# leaf_chaser.net
KiCad netlist of a schematic drawn in EasyEDA Pro
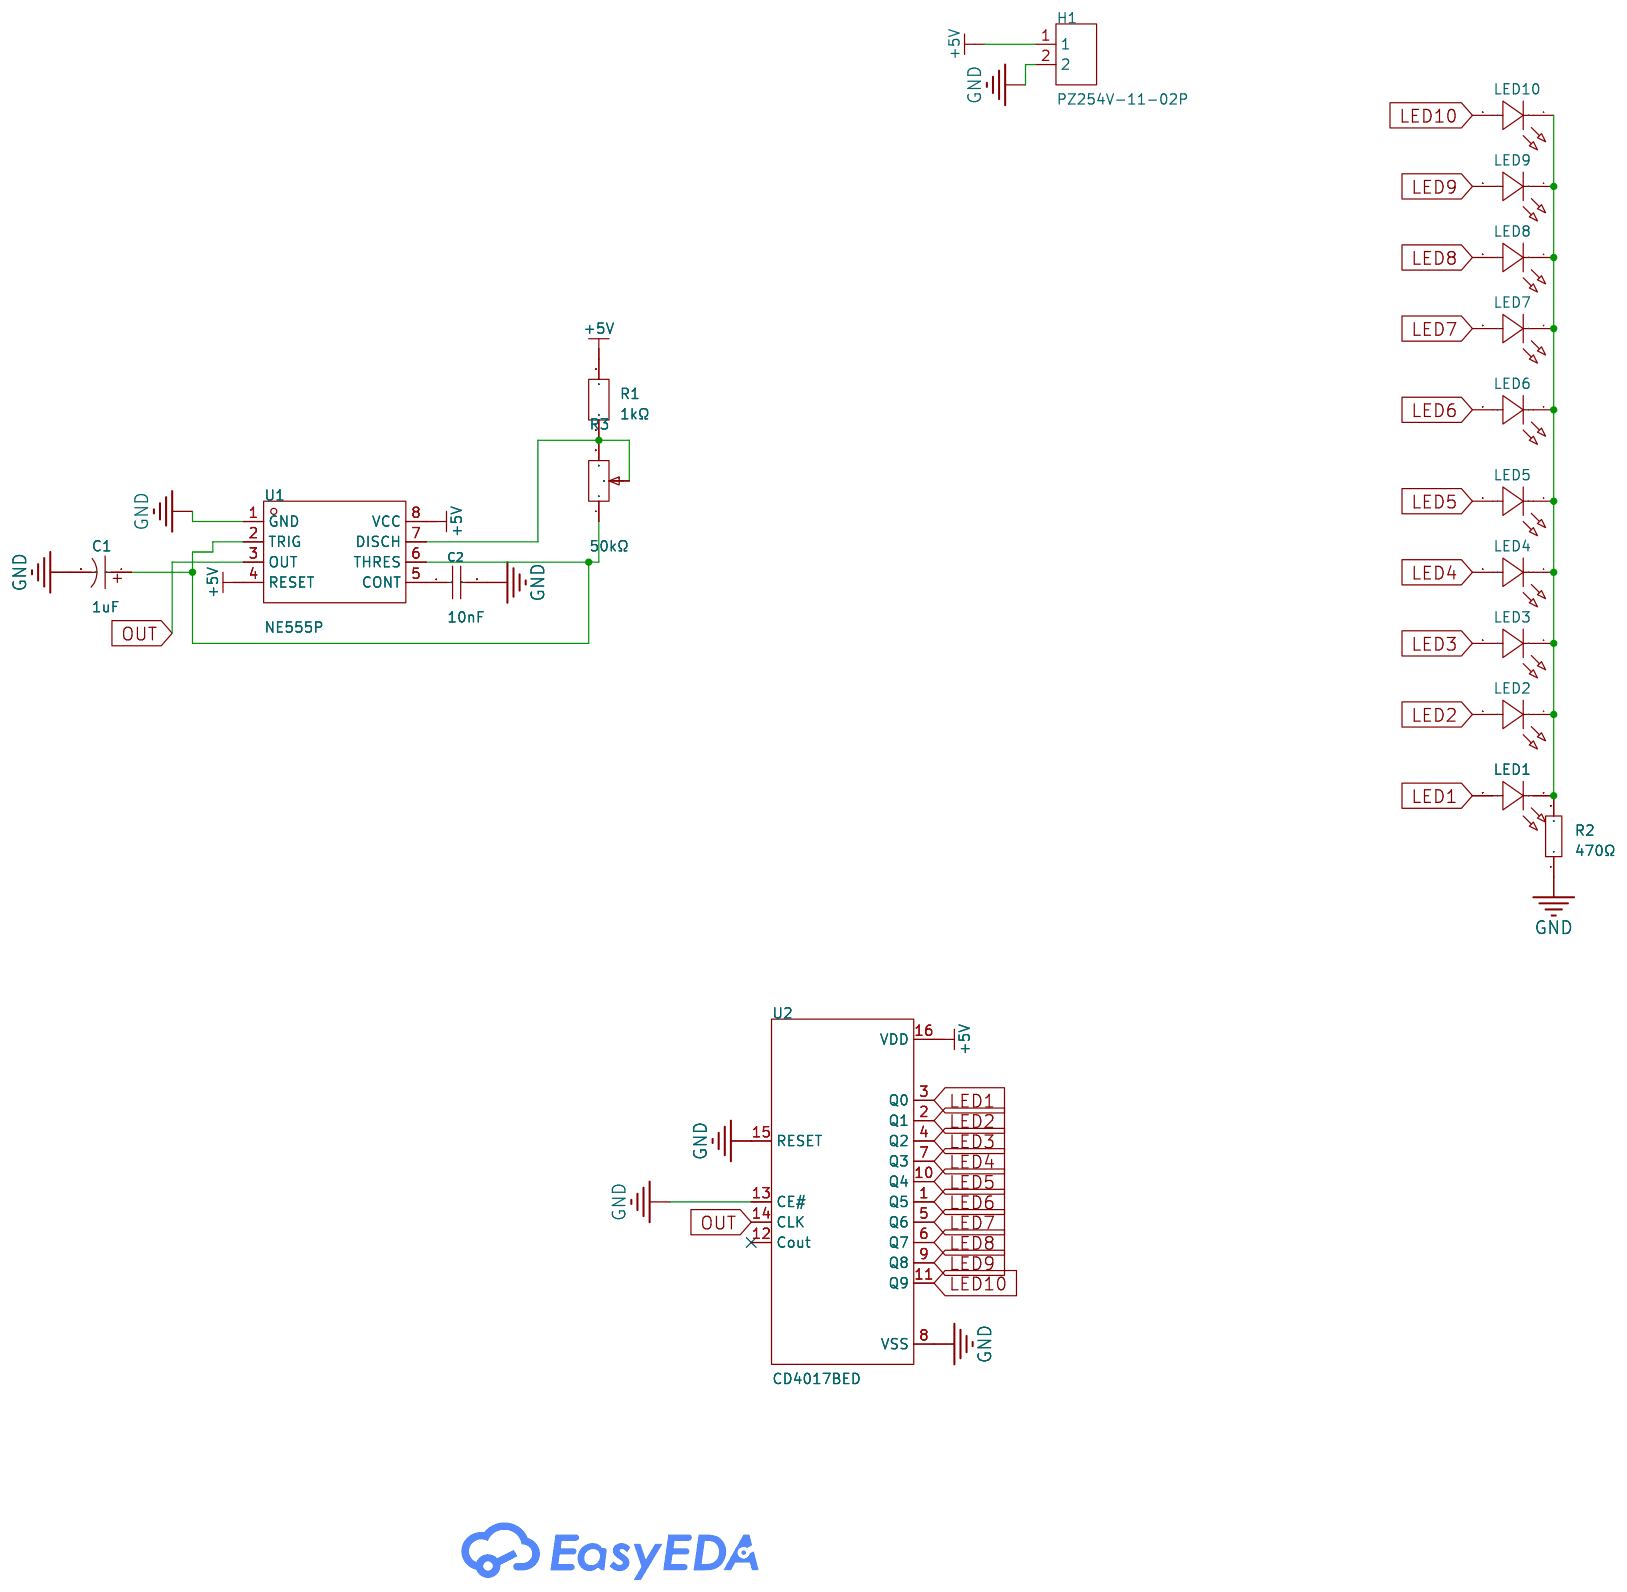
[diagram p0: schematic sheet]

(export (version "E")
  (design (tool "Eeschema 10.0.6"))
  (components
    (comp (ref "C1")
      (value "1uF")
      (footprint "easyedapro:CAP-TH_BD4.0-P1.50-D0.8-FD")
      (fields
        (field (name "Manufacturer Part") "KS1H010MB070A00CV0")
        (field (name "Manufacturer") "HUAWEI(华威集团)")
      )
      (libsource (lib "easyedapro") (part "KS1H010MB070A00CV0"))
    )
    (comp (ref "C2")
      (value "10nF")
      (footprint "easyedapro:C0603")
      (description "Capacitance:10nF Tolerance:±10% Tolerance:±10% Voltage Rating:50V Temperature Coefficient:X7R")
      (fields
        (field (name "Manufacturer Part") "CC0603KRX7R9BB103")
        (field (name "Manufacturer") "YAGEO(国巨)")
      )
      (libsource (lib "easyedapro") (part "CC0603KRX7R9BB103"))
    )
    (comp (ref "H1")
      (value "PZ254V-11-02P")
      (footprint "easyedapro:HDR-TH_2P-P2.54-V-M")
      (fields (field (name "Manufacturer") "XFCN(兴飞)"))
      (libsource (lib "easyedapro") (part "PZ254V-11-02P"))
    )
    (comp (ref "LED1")
      (value "XL-302SURD")
      (footprint "easyedapro:LED-TH_BD3.8-P2.54-RD")
      (fields (field (name "Manufacturer") "XINGLIGHT(成兴光)"))
      (libsource (lib "easyedapro") (part "XL-302SURD"))
    )
    (comp (ref "LED2")
      (value "XL-302SURD")
      (footprint "easyedapro:LED-TH_BD3.8-P2.54-RD")
      (fields (field (name "Manufacturer") "XINGLIGHT(成兴光)"))
      (libsource (lib "easyedapro") (part "XL-302SURD"))
    )
    (comp (ref "LED3")
      (value "XL-302SURD")
      (footprint "easyedapro:LED-TH_BD3.8-P2.54-RD")
      (fields (field (name "Manufacturer") "XINGLIGHT(成兴光)"))
      (libsource (lib "easyedapro") (part "XL-302SURD"))
    )
    (comp (ref "LED4")
      (value "XL-302SURD")
      (footprint "easyedapro:LED-TH_BD3.8-P2.54-RD")
      (fields (field (name "Manufacturer") "XINGLIGHT(成兴光)"))
      (libsource (lib "easyedapro") (part "XL-302SURD"))
    )
    (comp (ref "LED5")
      (value "XL-302SURD")
      (footprint "easyedapro:LED-TH_BD3.8-P2.54-RD")
      (fields (field (name "Manufacturer") "XINGLIGHT(成兴光)"))
      (libsource (lib "easyedapro") (part "XL-302SURD"))
    )
    (comp (ref "LED6")
      (value "XL-302SURD")
      (footprint "easyedapro:LED-TH_BD3.8-P2.54-RD")
      (fields (field (name "Manufacturer") "XINGLIGHT(成兴光)"))
      (libsource (lib "easyedapro") (part "XL-302SURD"))
    )
    (comp (ref "LED7")
      (value "XL-302SURD")
      (footprint "easyedapro:LED-TH_BD3.8-P2.54-RD")
      (fields (field (name "Manufacturer") "XINGLIGHT(成兴光)"))
      (libsource (lib "easyedapro") (part "XL-302SURD"))
    )
    (comp (ref "LED8")
      (value "XL-302SURD")
      (footprint "easyedapro:LED-TH_BD3.8-P2.54-RD")
      (fields (field (name "Manufacturer") "XINGLIGHT(成兴光)"))
      (libsource (lib "easyedapro") (part "XL-302SURD"))
    )
    (comp (ref "LED9")
      (value "XL-302SURD")
      (footprint "easyedapro:LED-TH_BD3.8-P2.54-RD")
      (fields (field (name "Manufacturer") "XINGLIGHT(成兴光)"))
      (libsource (lib "easyedapro") (part "XL-302SURD"))
    )
    (comp (ref "LED10")
      (value "XL-302SURD")
      (footprint "easyedapro:LED-TH_BD3.8-P2.54-RD")
      (fields (field (name "Manufacturer") "XINGLIGHT(成兴光)"))
      (libsource (lib "easyedapro") (part "XL-302SURD"))
    )
    (comp (ref "R1")
      (value "1kΩ")
      (footprint "easyedapro:RES-TH_BD2.7-L6.2-P10.20-D0.4")
      (fields (field (name "Manufacturer Part") "MF1/4W-1K±1%-ST52") (field (name "Manufacturer") "VO(翔胜)"))
      (libsource (lib "easyedapro") (part "MF1/4W-1K±1%-ST52"))
    )
    (comp (ref "R2")
      (value "470Ω")
      (footprint "easyedapro:RES-TH_BD2.3-L6.5-P10.50-D0.5")
      (fields
        (field (name "Manufacturer Part") "MF1/2WS-470Ω±1% T")
        (field (name "Manufacturer") "CCO(千志电子)")
      )
      (libsource (lib "easyedapro") (part "MF1/2WS-470Ω±1% T52"))
    )
    (comp (ref "R3")
      (value "50kΩ")
      (footprint "easyedapro:RES-ADJ-TH_3296W")
      (fields (field (name "Manufacturer Part") "3296W-1-503LF") (field (name "Manufacturer") "JIERR(捷而瑞)"))
      (libsource (lib "easyedapro") (part "3296W-1-503LF_C49190466"))
    )
    (comp (ref "U1")
      (value "NE555P")
      (footprint "easyedapro:DIP-8_L9.8-W6.6-P2.54-LS7.6-BL")
      (fields (field (name "Manufacturer") "TI(德州仪器)"))
      (libsource (lib "easyedapro") (part "NE555P"))
    )
    (comp (ref "U2")
      (value "CD4017BED")
      (footprint "easyedapro:PDIP-16_L19.7-W6.6-P2.54-LS7.6-BL")
      (fields (field (name "Manufacturer") "GMIC(绿微)"))
      (libsource (lib "easyedapro") (part "CD4017BED"))
    )
  )
  (nets
    (net (code "1") (name "+5V") (class "Default")
      (node (ref "H1") (pin "1") (pinfunction "1_1") (pintype "unspecified"))
      (node (ref "R1") (pin "2") (pinfunction "2_2") (pintype "unspecified"))
      (node (ref "U1") (pin "4") (pinfunction "RESET_4") (pintype "input"))
      (node (ref "U1") (pin "8") (pinfunction "VCC_8") (pintype "input"))
      (node (ref "U2") (pin "16") (pinfunction "VDD_16") (pintype "unspecified"))
    )
    (net (code "2") (name "GND") (class "Default")
      (node (ref "C1") (pin "2") (pinfunction "2_2") (pintype "input"))
      (node (ref "C2") (pin "2") (pinfunction "2_2") (pintype "input"))
      (node (ref "H1") (pin "2") (pinfunction "2_2") (pintype "unspecified"))
      (node (ref "R2") (pin "1") (pinfunction "1_1") (pintype "unspecified"))
      (node (ref "U1") (pin "1") (pinfunction "GND_1") (pintype "input"))
      (node (ref "U2") (pin "13") (pinfunction "CE#_13") (pintype "unspecified"))
      (node (ref "U2") (pin "15") (pinfunction "RESET_15") (pintype "unspecified"))
      (node (ref "U2") (pin "8") (pinfunction "VSS_8") (pintype "unspecified"))
    )
    (net (code "3") (name "LED1") (class "Default")
      (node (ref "LED1") (pin "2") (pinfunction "A_2") (pintype "unspecified"))
      (node (ref "U2") (pin "3") (pinfunction "Q0_3") (pintype "unspecified"))
    )
    (net (code "4") (name "LED2") (class "Default")
      (node (ref "LED2") (pin "2") (pinfunction "A_2") (pintype "unspecified"))
      (node (ref "U2") (pin "2") (pinfunction "Q1_2") (pintype "unspecified"))
    )
    (net (code "5") (name "LED3") (class "Default")
      (node (ref "LED3") (pin "2") (pinfunction "A_2") (pintype "unspecified"))
      (node (ref "U2") (pin "4") (pinfunction "Q2_4") (pintype "unspecified"))
    )
    (net (code "6") (name "LED4") (class "Default")
      (node (ref "LED4") (pin "2") (pinfunction "A_2") (pintype "unspecified"))
      (node (ref "U2") (pin "7") (pinfunction "Q3_7") (pintype "unspecified"))
    )
    (net (code "7") (name "LED5") (class "Default")
      (node (ref "LED5") (pin "2") (pinfunction "A_2") (pintype "unspecified"))
      (node (ref "U2") (pin "10") (pinfunction "Q4_10") (pintype "unspecified"))
    )
    (net (code "8") (name "LED6") (class "Default")
      (node (ref "LED6") (pin "2") (pinfunction "A_2") (pintype "unspecified"))
      (node (ref "U2") (pin "1") (pinfunction "Q5_1") (pintype "unspecified"))
    )
    (net (code "9") (name "LED7") (class "Default")
      (node (ref "LED7") (pin "2") (pinfunction "A_2") (pintype "unspecified"))
      (node (ref "U2") (pin "5") (pinfunction "Q6_5") (pintype "unspecified"))
    )
    (net (code "10") (name "LED8") (class "Default")
      (node (ref "LED8") (pin "2") (pinfunction "A_2") (pintype "unspecified"))
      (node (ref "U2") (pin "6") (pinfunction "Q7_6") (pintype "unspecified"))
    )
    (net (code "11") (name "LED9") (class "Default")
      (node (ref "LED9") (pin "2") (pinfunction "A_2") (pintype "unspecified"))
      (node (ref "U2") (pin "9") (pinfunction "Q8_9") (pintype "unspecified"))
    )
    (net (code "12") (name "LED10") (class "Default")
      (node (ref "LED10") (pin "2") (pinfunction "A_2") (pintype "unspecified"))
      (node (ref "U2") (pin "11") (pinfunction "Q9_11") (pintype "unspecified"))
    )
    (net (code "13") (name "Net-(LED1-K)") (class "Default")
      (node (ref "LED1") (pin "1") (pinfunction "K_1") (pintype "unspecified"))
      (node (ref "LED10") (pin "1") (pinfunction "K_1") (pintype "unspecified"))
      (node (ref "LED2") (pin "1") (pinfunction "K_1") (pintype "unspecified"))
      (node (ref "LED3") (pin "1") (pinfunction "K_1") (pintype "unspecified"))
      (node (ref "LED4") (pin "1") (pinfunction "K_1") (pintype "unspecified"))
      (node (ref "LED5") (pin "1") (pinfunction "K_1") (pintype "unspecified"))
      (node (ref "LED6") (pin "1") (pinfunction "K_1") (pintype "unspecified"))
      (node (ref "LED7") (pin "1") (pinfunction "K_1") (pintype "unspecified"))
      (node (ref "LED8") (pin "1") (pinfunction "K_1") (pintype "unspecified"))
      (node (ref "LED9") (pin "1") (pinfunction "K_1") (pintype "unspecified"))
      (node (ref "R2") (pin "2") (pinfunction "2_2") (pintype "unspecified"))
    )
    (net (code "14") (name "Net-(U1-CONT)") (class "Default")
      (node (ref "C2") (pin "1") (pinfunction "1_1") (pintype "input"))
      (node (ref "U1") (pin "5") (pinfunction "CONT_5") (pintype "input"))
    )
    (net (code "15") (name "Net-(U1-DISCH)") (class "Default")
      (node (ref "R1") (pin "1") (pinfunction "1_1") (pintype "unspecified"))
      (node (ref "R3") (pin "2") (pinfunction "2_2") (pintype "input"))
      (node (ref "R3") (pin "3") (pinfunction "3_3") (pintype "input"))
      (node (ref "U1") (pin "7") (pinfunction "DISCH_7") (pintype "input"))
    )
    (net (code "16") (name "Net-(U1-THRES)") (class "Default")
      (node (ref "C1") (pin "1") (pinfunction "1_1") (pintype "input"))
      (node (ref "R3") (pin "1") (pinfunction "1_1") (pintype "input"))
      (node (ref "U1") (pin "2") (pinfunction "TRIG_2") (pintype "input"))
      (node (ref "U1") (pin "6") (pinfunction "THRES_6") (pintype "input"))
    )
    (net (code "17") (name "OUT") (class "Default")
      (node (ref "U1") (pin "3") (pinfunction "OUT_3") (pintype "input"))
      (node (ref "U2") (pin "14") (pinfunction "CLK_14") (pintype "unspecified"))
    )
    (net (code "18") (name "unconnected-(U2-Cout-Pad12)") (class "Default")
      (node (ref "U2") (pin "12") (pinfunction "Cout_12") (pintype "unspecified+no_connect"))
    )
  )
)
